# cc.net
KiCad netlist of a schematic drawn in EAGLE
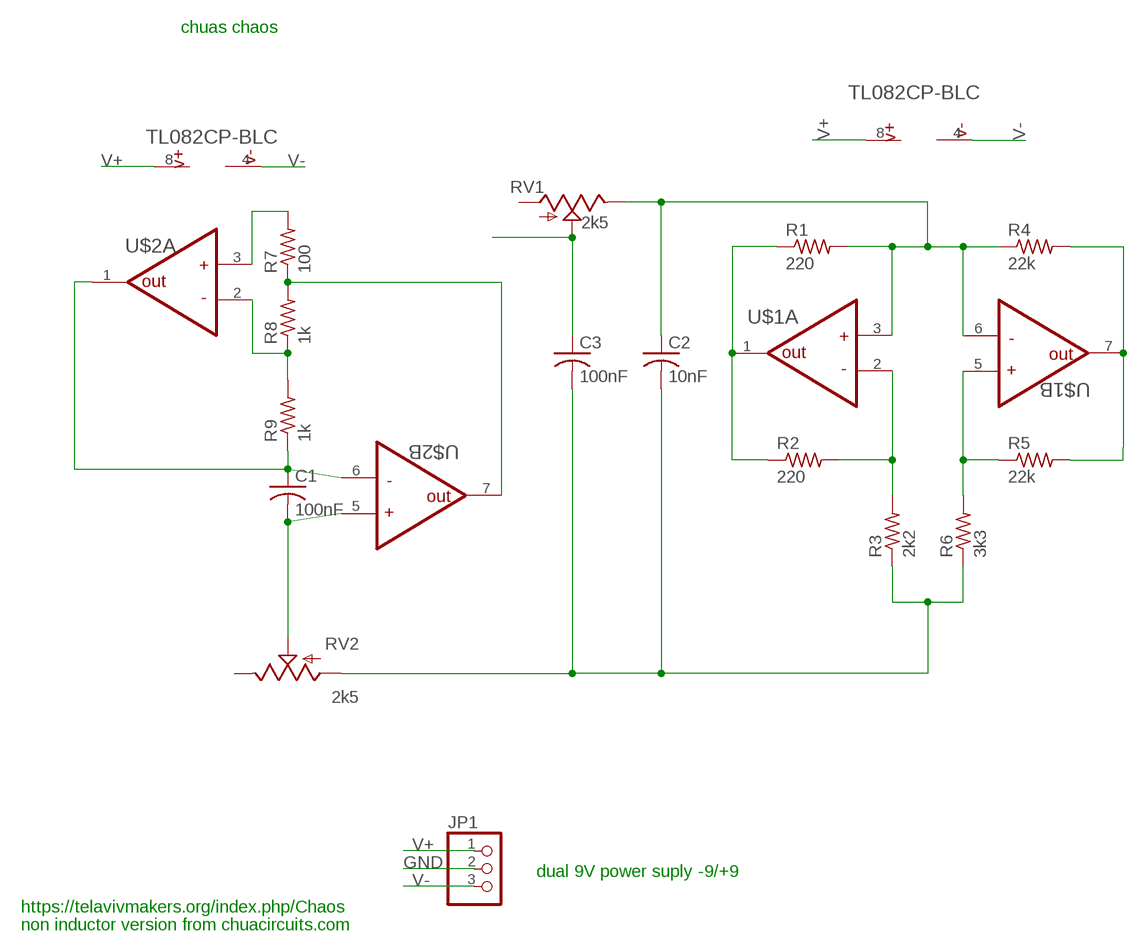
[diagram p0: schematic, sheet 1]

(export (version "E")
  (design (tool "Eeschema 10.0.6"))
  (components
    (comp (ref "C1")
      (value "100nF")
      (footprint "eagle-import:C025-024X044")
      (libsource (lib "eagle-import") (part "C-US025-024X044"))
    )
    (comp (ref "C2")
      (value "10nF")
      (footprint "eagle-import:C025-024X044")
      (libsource (lib "eagle-import") (part "C-US025-024X044"))
    )
    (comp (ref "C3")
      (value "100nF")
      (footprint "eagle-import:C025-024X044")
      (libsource (lib "eagle-import") (part "C-US025-024X044"))
    )
    (comp (ref "JP1")
      (value "PINHD-1X3")
      (footprint "eagle-import:1X03")
      (libsource (lib "eagle-import") (part "PINHD-1X3"))
    )
    (comp (ref "R1")
      (value "220")
      (footprint "eagle-import:0204_5")
      (libsource (lib "eagle-import") (part "R-US_0204/5"))
    )
    (comp (ref "R2")
      (value "220")
      (footprint "eagle-import:0204_5")
      (libsource (lib "eagle-import") (part "R-US_0204/5"))
    )
    (comp (ref "R3")
      (value "2k2")
      (footprint "eagle-import:0204_5")
      (libsource (lib "eagle-import") (part "R-US_0204/5"))
    )
    (comp (ref "R4")
      (value "22k")
      (footprint "eagle-import:0204_5")
      (libsource (lib "eagle-import") (part "R-US_0204/5"))
    )
    (comp (ref "R5")
      (value "22k")
      (footprint "eagle-import:0204_5")
      (libsource (lib "eagle-import") (part "R-US_0204/5"))
    )
    (comp (ref "R6")
      (value "3k3")
      (footprint "eagle-import:0204_5")
      (libsource (lib "eagle-import") (part "R-US_0204/5"))
    )
    (comp (ref "R7")
      (value "100")
      (footprint "eagle-import:0204_5")
      (libsource (lib "eagle-import") (part "R-US_0204/5"))
    )
    (comp (ref "R8")
      (value "1k")
      (footprint "eagle-import:0204_5")
      (libsource (lib "eagle-import") (part "R-US_0204/5"))
    )
    (comp (ref "R9")
      (value "1k")
      (footprint "eagle-import:0204_5")
      (libsource (lib "eagle-import") (part "R-US_0204/5"))
    )
    (comp (ref "RV1")
      (value "2k5")
      (footprint "eagle-import:POT_ALPHA_RV16AF-20")
      (libsource (lib "eagle-import") (part "POT-RV16AF-20"))
    )
    (comp (ref "RV2")
      (value "2k5")
      (footprint "eagle-import:POT_ALPHA_RV16AF-20")
      (libsource (lib "eagle-import") (part "POT-RV16AF-20"))
    )
    (comp (ref "U$1")
      (value "TL082CP-BLC")
      (footprint "eagle-import:DIP254P762X508-8")
      (libsource (lib "eagle-import") (part "TL082CP-BLC"))
    )
    (comp (ref "U$2")
      (value "TL082CP-BLC")
      (footprint "eagle-import:DIP254P762X508-8")
      (libsource (lib "eagle-import") (part "TL082CP-BLC"))
    )
  )
  (nets
    (net (code "1") (name "/GND") (class "Default")
      (node (ref "JP1") (pin "2") (pinfunction "2_2") (pintype "passive"))
    )
    (net (code "2") (name "/V+") (class "Default")
      (node (ref "JP1") (pin "1") (pinfunction "1_1") (pintype "passive"))
      (node (ref "U$1") (pin "8") (pinfunction "P$1_8") (pintype "power_in"))
      (node (ref "U$2") (pin "8") (pinfunction "P$1_8") (pintype "power_in"))
    )
    (net (code "3") (name "/V-") (class "Default")
      (node (ref "JP1") (pin "3") (pinfunction "3_3") (pintype "passive"))
      (node (ref "U$1") (pin "4") (pinfunction "P$2_4") (pintype "power_in"))
      (node (ref "U$2") (pin "4") (pinfunction "P$2_4") (pintype "power_in"))
    )
    (net (code "4") (name "Net-(RV1-E)") (class "Default")
      (node (ref "C2") (pin "1") (pinfunction "1_1") (pintype "passive"))
      (node (ref "R1") (pin "2") (pinfunction "2_2") (pintype "passive"))
      (node (ref "R4") (pin "1") (pinfunction "1_1") (pintype "passive"))
      (node (ref "RV1") (pin "3") (pinfunction "E_3") (pintype "passive"))
      (node (ref "U$1") (pin "3") (pinfunction "+_3") (pintype "bidirectional"))
      (node (ref "U$1") (pin "6") (pinfunction "-_6") (pintype "bidirectional"))
    )
    (net (code "5") (name "Net-(RV1-S)") (class "Default")
      (node (ref "C3") (pin "1") (pinfunction "1_1") (pintype "passive"))
      (node (ref "RV1") (pin "2") (pinfunction "S_2") (pintype "passive"))
    )
    (net (code "6") (name "Net-(RV2-A)") (class "Default")
      (node (ref "C2") (pin "2") (pinfunction "2_2") (pintype "passive"))
      (node (ref "C3") (pin "2") (pinfunction "2_2") (pintype "passive"))
      (node (ref "R3") (pin "1") (pinfunction "1_1") (pintype "passive"))
      (node (ref "R6") (pin "1") (pinfunction "1_1") (pintype "passive"))
      (node (ref "RV2") (pin "1") (pinfunction "A_1") (pintype "passive"))
    )
    (net (code "7") (name "Net-(RV2-S)") (class "Default")
      (node (ref "C1") (pin "2") (pinfunction "2_2") (pintype "passive"))
      (node (ref "RV2") (pin "2") (pinfunction "S_2") (pintype "passive"))
      (node (ref "U$2") (pin "5") (pinfunction "+_5") (pintype "bidirectional"))
    )
    (net (code "8") (name "Net-(U$1A--)") (class "Default")
      (node (ref "R2") (pin "2") (pinfunction "2_2") (pintype "passive"))
      (node (ref "R3") (pin "2") (pinfunction "2_2") (pintype "passive"))
      (node (ref "U$1") (pin "2") (pinfunction "-_2") (pintype "bidirectional"))
    )
    (net (code "9") (name "Net-(U$1A-OUT)") (class "Default")
      (node (ref "R1") (pin "1") (pinfunction "1_1") (pintype "passive"))
      (node (ref "R2") (pin "1") (pinfunction "1_1") (pintype "passive"))
      (node (ref "U$1") (pin "1") (pinfunction "OUT_1") (pintype "bidirectional"))
    )
    (net (code "10") (name "Net-(U$1B-+)") (class "Default")
      (node (ref "R5") (pin "1") (pinfunction "1_1") (pintype "passive"))
      (node (ref "R6") (pin "2") (pinfunction "2_2") (pintype "passive"))
      (node (ref "U$1") (pin "5") (pinfunction "+_5") (pintype "bidirectional"))
    )
    (net (code "11") (name "Net-(U$1B-OUT)") (class "Default")
      (node (ref "R4") (pin "2") (pinfunction "2_2") (pintype "passive"))
      (node (ref "R5") (pin "2") (pinfunction "2_2") (pintype "passive"))
      (node (ref "U$1") (pin "7") (pinfunction "OUT_7") (pintype "bidirectional"))
    )
    (net (code "12") (name "Net-(U$2A-+)") (class "Default")
      (node (ref "R7") (pin "2") (pinfunction "2_2") (pintype "passive"))
      (node (ref "U$2") (pin "3") (pinfunction "+_3") (pintype "bidirectional"))
    )
    (net (code "13") (name "Net-(U$2A--)") (class "Default")
      (node (ref "R8") (pin "1") (pinfunction "1_1") (pintype "passive"))
      (node (ref "R9") (pin "2") (pinfunction "2_2") (pintype "passive"))
      (node (ref "U$2") (pin "2") (pinfunction "-_2") (pintype "bidirectional"))
    )
    (net (code "14") (name "Net-(U$2A-OUT)") (class "Default")
      (node (ref "C1") (pin "1") (pinfunction "1_1") (pintype "passive"))
      (node (ref "R9") (pin "1") (pinfunction "1_1") (pintype "passive"))
      (node (ref "U$2") (pin "1") (pinfunction "OUT_1") (pintype "bidirectional"))
      (node (ref "U$2") (pin "6") (pinfunction "-_6") (pintype "bidirectional"))
    )
    (net (code "15") (name "Net-(U$2B-OUT)") (class "Default")
      (node (ref "R7") (pin "1") (pinfunction "1_1") (pintype "passive"))
      (node (ref "R8") (pin "2") (pinfunction "2_2") (pintype "passive"))
      (node (ref "U$2") (pin "7") (pinfunction "OUT_7") (pintype "bidirectional"))
    )
    (net (code "16") (name "unconnected-(RV1-A-Pad1)") (class "Default")
      (node (ref "RV1") (pin "1") (pinfunction "A_1") (pintype "passive"))
    )
    (net (code "17") (name "unconnected-(RV2-E-Pad3)") (class "Default")
      (node (ref "RV2") (pin "3") (pinfunction "E_3") (pintype "passive"))
    )
  )
)
